# URC-PASSTHROUGH.net
KiCad netlist of a schematic drawn in EAGLE
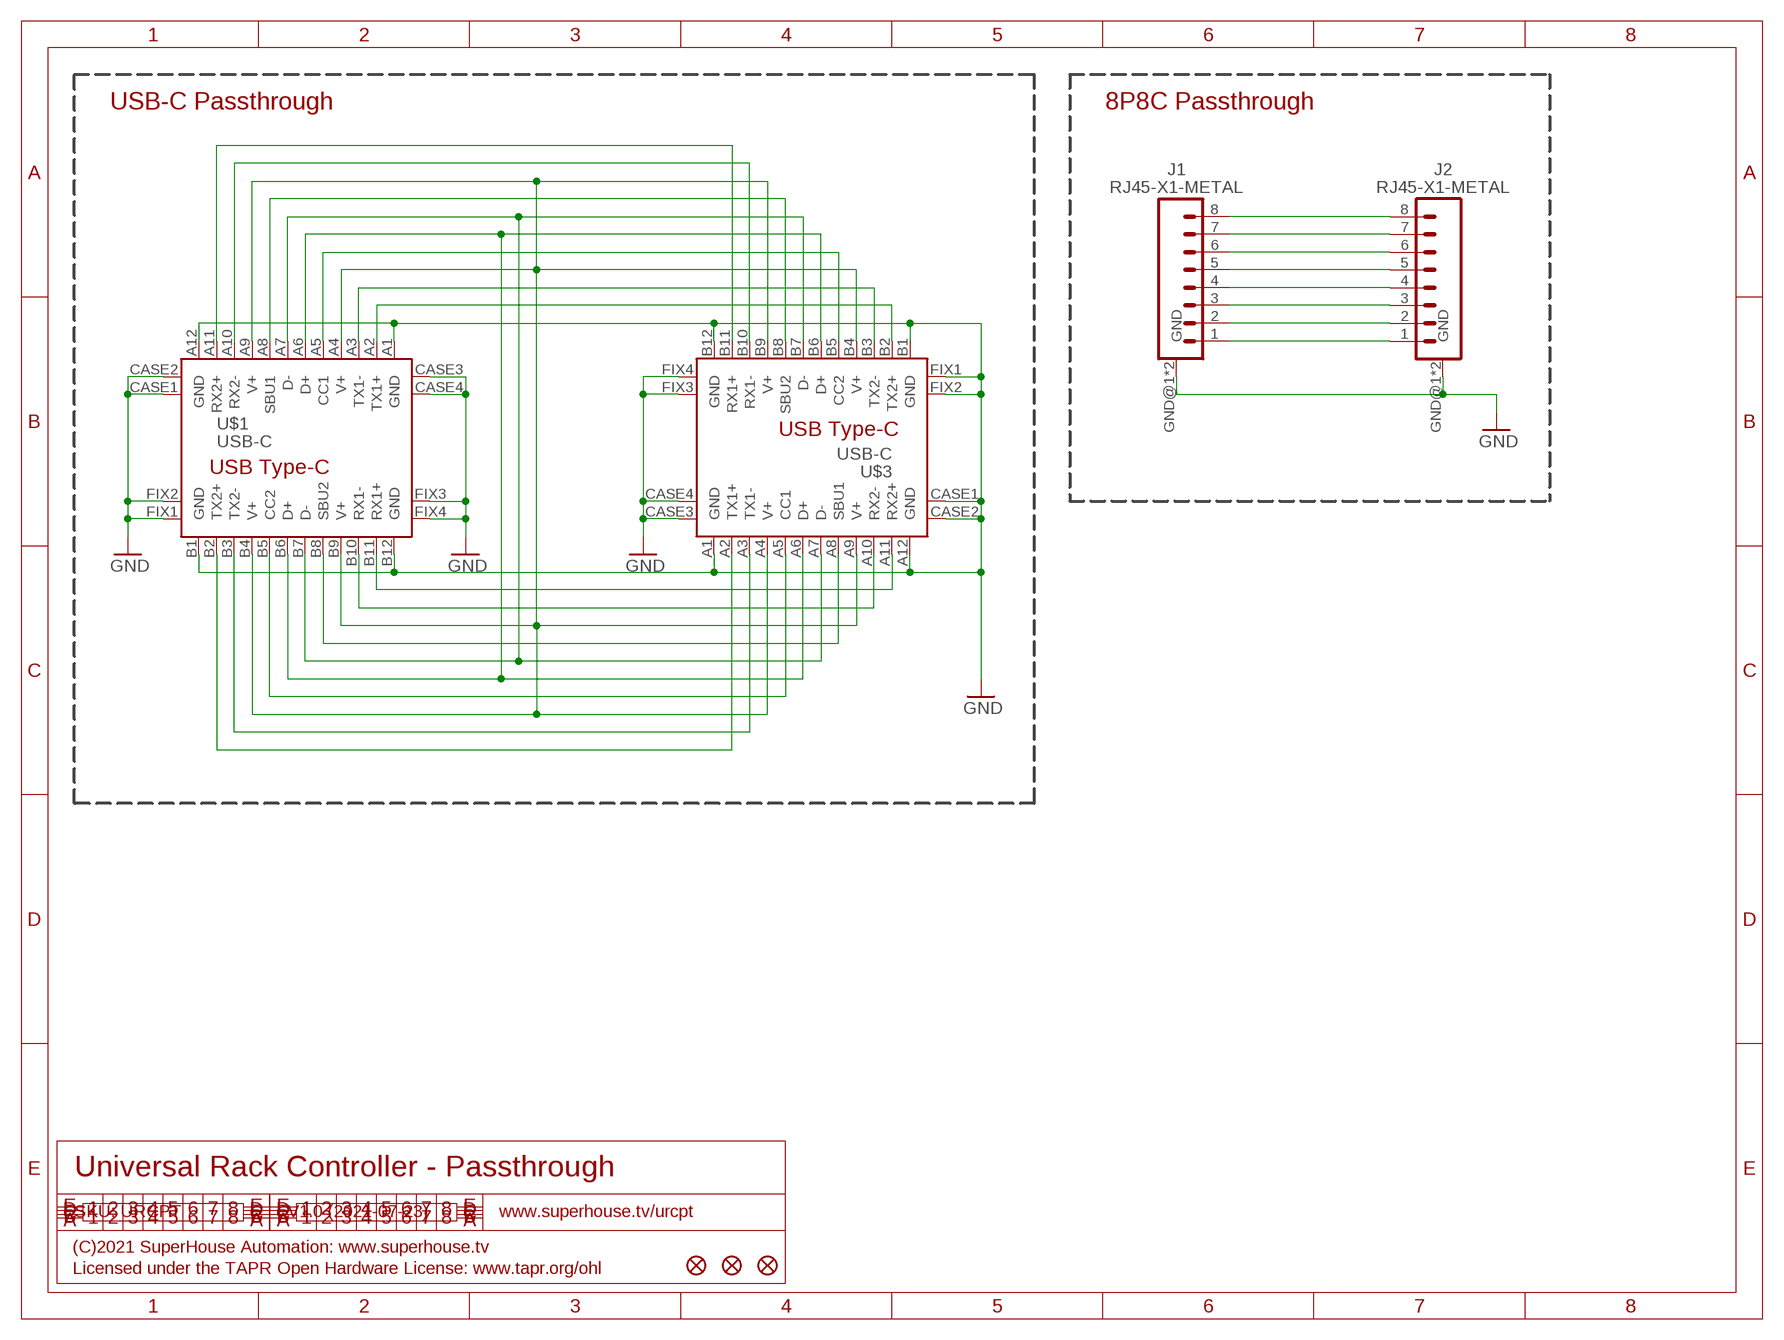
[diagram p0: schematic, sheet 1]

(export (version "E")
  (design (tool "Eeschema 10.0.6"))
  (components
    (comp (ref "FID1")
      (value "FIDUCIAL1X2.5")
      (footprint "eagle-import:FIDUCIAL-1X2.5")
      (libsource (lib "eagle-import") (part "FIDUCIAL1X2.5"))
    )
    (comp (ref "FID2")
      (value "FIDUCIAL1X2.5")
      (footprint "eagle-import:FIDUCIAL-1X2.5")
      (libsource (lib "eagle-import") (part "FIDUCIAL1X2.5"))
    )
    (comp (ref "FID3")
      (value "FIDUCIAL1X2.5")
      (footprint "eagle-import:FIDUCIAL-1X2.5")
      (libsource (lib "eagle-import") (part "FIDUCIAL1X2.5"))
    )
    (comp (ref "J1")
      (value "RJ45-X1-METAL")
      (footprint "eagle-import:RJ45-1X1")
      (libsource (lib "eagle-import") (part "RJ45-X1-METAL"))
    )
    (comp (ref "J2")
      (value "RJ45-X1-METAL")
      (footprint "eagle-import:RJ45-1X1")
      (libsource (lib "eagle-import") (part "RJ45-X1-METAL"))
    )
    (comp (ref "U$1")
      (value "USB-C")
      (footprint "eagle-import:USB-C-U52A")
      (libsource (lib "eagle-import") (part "USB-C"))
    )
    (comp (ref "U$3")
      (value "USB-C")
      (footprint "eagle-import:USB-C-U52A")
      (libsource (lib "eagle-import") (part "USB-C"))
    )
  )
  (nets
    (net (code "1") (name "GND") (class "Default")
      (node (ref "J1") (pin "GND@1") (pinfunction "GND_GND@1") (pintype "bidirectional"))
      (node (ref "J1") (pin "GND@2") (pinfunction "GND_GND@2") (pintype "bidirectional"))
      (node (ref "J2") (pin "GND@1") (pinfunction "GND_GND@1") (pintype "bidirectional"))
      (node (ref "J2") (pin "GND@2") (pinfunction "GND_GND@2") (pintype "bidirectional"))
      (node (ref "U$1") (pin "A1") (pinfunction "GND_A1") (pintype "power_in"))
      (node (ref "U$1") (pin "A12") (pinfunction "GND_A12") (pintype "power_in"))
      (node (ref "U$1") (pin "B1") (pinfunction "GND_B1") (pintype "power_in"))
      (node (ref "U$1") (pin "B12") (pinfunction "GND_B12") (pintype "power_in"))
      (node (ref "U$1") (pin "CASE1") (pinfunction "GND_CASE1") (pintype "power_in"))
      (node (ref "U$1") (pin "CASE2") (pinfunction "GND_CASE2") (pintype "power_in"))
      (node (ref "U$1") (pin "CASE3") (pinfunction "GND_CASE3") (pintype "power_in"))
      (node (ref "U$1") (pin "CASE4") (pinfunction "GND_CASE4") (pintype "power_in"))
      (node (ref "U$1") (pin "FIX1") (pinfunction "GND_FIX1") (pintype "power_in"))
      (node (ref "U$1") (pin "FIX2") (pinfunction "GND_FIX2") (pintype "power_in"))
      (node (ref "U$1") (pin "FIX3") (pinfunction "GND_FIX3") (pintype "power_in"))
      (node (ref "U$1") (pin "FIX4") (pinfunction "GND_FIX4") (pintype "power_in"))
      (node (ref "U$3") (pin "A1") (pinfunction "GND_A1") (pintype "power_in"))
      (node (ref "U$3") (pin "A12") (pinfunction "GND_A12") (pintype "power_in"))
      (node (ref "U$3") (pin "B1") (pinfunction "GND_B1") (pintype "power_in"))
      (node (ref "U$3") (pin "B12") (pinfunction "GND_B12") (pintype "power_in"))
      (node (ref "U$3") (pin "CASE1") (pinfunction "GND_CASE1") (pintype "power_in"))
      (node (ref "U$3") (pin "CASE2") (pinfunction "GND_CASE2") (pintype "power_in"))
      (node (ref "U$3") (pin "CASE3") (pinfunction "GND_CASE3") (pintype "power_in"))
      (node (ref "U$3") (pin "CASE4") (pinfunction "GND_CASE4") (pintype "power_in"))
      (node (ref "U$3") (pin "FIX1") (pinfunction "GND_FIX1") (pintype "power_in"))
      (node (ref "U$3") (pin "FIX2") (pinfunction "GND_FIX2") (pintype "power_in"))
      (node (ref "U$3") (pin "FIX3") (pinfunction "GND_FIX3") (pintype "power_in"))
      (node (ref "U$3") (pin "FIX4") (pinfunction "GND_FIX4") (pintype "power_in"))
    )
    (net (code "2") (name "Net-(J1-Pad1)") (class "Default")
      (node (ref "J1") (pin "1") (pinfunction "1_1") (pintype "passive"))
      (node (ref "J2") (pin "1") (pinfunction "1_1") (pintype "passive"))
    )
    (net (code "3") (name "Net-(J1-Pad2)") (class "Default")
      (node (ref "J1") (pin "2") (pinfunction "2_2") (pintype "passive"))
      (node (ref "J2") (pin "2") (pinfunction "2_2") (pintype "passive"))
    )
    (net (code "4") (name "Net-(J1-Pad3)") (class "Default")
      (node (ref "J1") (pin "3") (pinfunction "3_3") (pintype "passive"))
      (node (ref "J2") (pin "3") (pinfunction "3_3") (pintype "passive"))
    )
    (net (code "5") (name "Net-(J1-Pad4)") (class "Default")
      (node (ref "J1") (pin "4") (pinfunction "4_4") (pintype "passive"))
      (node (ref "J2") (pin "4") (pinfunction "4_4") (pintype "passive"))
    )
    (net (code "6") (name "Net-(J1-Pad5)") (class "Default")
      (node (ref "J1") (pin "5") (pinfunction "5_5") (pintype "passive"))
      (node (ref "J2") (pin "5") (pinfunction "5_5") (pintype "passive"))
    )
    (net (code "7") (name "Net-(J1-Pad6)") (class "Default")
      (node (ref "J1") (pin "6") (pinfunction "6_6") (pintype "passive"))
      (node (ref "J2") (pin "6") (pinfunction "6_6") (pintype "passive"))
    )
    (net (code "8") (name "Net-(J1-Pad7)") (class "Default")
      (node (ref "J1") (pin "7") (pinfunction "7_7") (pintype "passive"))
      (node (ref "J2") (pin "7") (pinfunction "7_7") (pintype "passive"))
    )
    (net (code "9") (name "Net-(J1-Pad8)") (class "Default")
      (node (ref "J1") (pin "8") (pinfunction "8_8") (pintype "passive"))
      (node (ref "J2") (pin "8") (pinfunction "8_8") (pintype "passive"))
    )
    (net (code "10") (name "Net-(U$1-CC1)") (class "Default")
      (node (ref "U$1") (pin "A5") (pinfunction "CC1_A5") (pintype "bidirectional"))
      (node (ref "U$3") (pin "B5") (pinfunction "CC2_B5") (pintype "bidirectional"))
    )
    (net (code "11") (name "Net-(U$1-CC2)") (class "Default")
      (node (ref "U$1") (pin "B5") (pinfunction "CC2_B5") (pintype "bidirectional"))
      (node (ref "U$3") (pin "A5") (pinfunction "CC1_A5") (pintype "bidirectional"))
    )
    (net (code "12") (name "Net-(U$1-D+-PadA6)") (class "Default")
      (node (ref "U$1") (pin "A6") (pinfunction "D+_A6") (pintype "bidirectional"))
      (node (ref "U$1") (pin "B6") (pinfunction "D+_B6") (pintype "bidirectional"))
      (node (ref "U$3") (pin "A6") (pinfunction "D+_A6") (pintype "bidirectional"))
      (node (ref "U$3") (pin "B6") (pinfunction "D+_B6") (pintype "bidirectional"))
    )
    (net (code "13") (name "Net-(U$1-D--PadA7)") (class "Default")
      (node (ref "U$1") (pin "A7") (pinfunction "D-_A7") (pintype "bidirectional"))
      (node (ref "U$1") (pin "B7") (pinfunction "D-_B7") (pintype "bidirectional"))
      (node (ref "U$3") (pin "A7") (pinfunction "D-_A7") (pintype "bidirectional"))
      (node (ref "U$3") (pin "B7") (pinfunction "D-_B7") (pintype "bidirectional"))
    )
    (net (code "14") (name "Net-(U$1-RX1+)") (class "Default")
      (node (ref "U$1") (pin "B11") (pinfunction "RX1+_B11") (pintype "bidirectional"))
      (node (ref "U$3") (pin "A11") (pinfunction "RX2+_A11") (pintype "bidirectional"))
    )
    (net (code "15") (name "Net-(U$1-RX1-)") (class "Default")
      (node (ref "U$1") (pin "B10") (pinfunction "RX1-_B10") (pintype "bidirectional"))
      (node (ref "U$3") (pin "A10") (pinfunction "RX2-_A10") (pintype "bidirectional"))
    )
    (net (code "16") (name "Net-(U$1-RX2+)") (class "Default")
      (node (ref "U$1") (pin "A11") (pinfunction "RX2+_A11") (pintype "bidirectional"))
      (node (ref "U$3") (pin "B11") (pinfunction "RX1+_B11") (pintype "bidirectional"))
    )
    (net (code "17") (name "Net-(U$1-RX2-)") (class "Default")
      (node (ref "U$1") (pin "A10") (pinfunction "RX2-_A10") (pintype "bidirectional"))
      (node (ref "U$3") (pin "B10") (pinfunction "RX1-_B10") (pintype "bidirectional"))
    )
    (net (code "18") (name "Net-(U$1-SBU1)") (class "Default")
      (node (ref "U$1") (pin "A8") (pinfunction "SBU1_A8") (pintype "bidirectional"))
      (node (ref "U$3") (pin "B8") (pinfunction "SBU2_B8") (pintype "bidirectional"))
    )
    (net (code "19") (name "Net-(U$1-SBU2)") (class "Default")
      (node (ref "U$1") (pin "B8") (pinfunction "SBU2_B8") (pintype "bidirectional"))
      (node (ref "U$3") (pin "A8") (pinfunction "SBU1_A8") (pintype "bidirectional"))
    )
    (net (code "20") (name "Net-(U$1-TX1+)") (class "Default")
      (node (ref "U$1") (pin "A2") (pinfunction "TX1+_A2") (pintype "bidirectional"))
      (node (ref "U$3") (pin "B2") (pinfunction "TX2+_B2") (pintype "bidirectional"))
    )
    (net (code "21") (name "Net-(U$1-TX1-)") (class "Default")
      (node (ref "U$1") (pin "A3") (pinfunction "TX1-_A3") (pintype "bidirectional"))
      (node (ref "U$3") (pin "B3") (pinfunction "TX2-_B3") (pintype "bidirectional"))
    )
    (net (code "22") (name "Net-(U$1-TX2+)") (class "Default")
      (node (ref "U$1") (pin "B2") (pinfunction "TX2+_B2") (pintype "bidirectional"))
      (node (ref "U$3") (pin "A2") (pinfunction "TX1+_A2") (pintype "bidirectional"))
    )
    (net (code "23") (name "Net-(U$1-TX2-)") (class "Default")
      (node (ref "U$1") (pin "B3") (pinfunction "TX2-_B3") (pintype "bidirectional"))
      (node (ref "U$3") (pin "A3") (pinfunction "TX1-_A3") (pintype "bidirectional"))
    )
    (net (code "24") (name "Net-(U$1-V+-PadA4)") (class "Default")
      (node (ref "U$1") (pin "A4") (pinfunction "V+_A4") (pintype "power_in"))
      (node (ref "U$1") (pin "A9") (pinfunction "V+_A9") (pintype "power_in"))
      (node (ref "U$1") (pin "B4") (pinfunction "V+_B4") (pintype "power_in"))
      (node (ref "U$1") (pin "B9") (pinfunction "V+_B9") (pintype "power_in"))
      (node (ref "U$3") (pin "A4") (pinfunction "V+_A4") (pintype "power_in"))
      (node (ref "U$3") (pin "A9") (pinfunction "V+_A9") (pintype "power_in"))
      (node (ref "U$3") (pin "B4") (pinfunction "V+_B4") (pintype "power_in"))
      (node (ref "U$3") (pin "B9") (pinfunction "V+_B9") (pintype "power_in"))
    )
  )
)
